# H_Driver.net
KiCad netlist of a schematic drawn in EAGLE
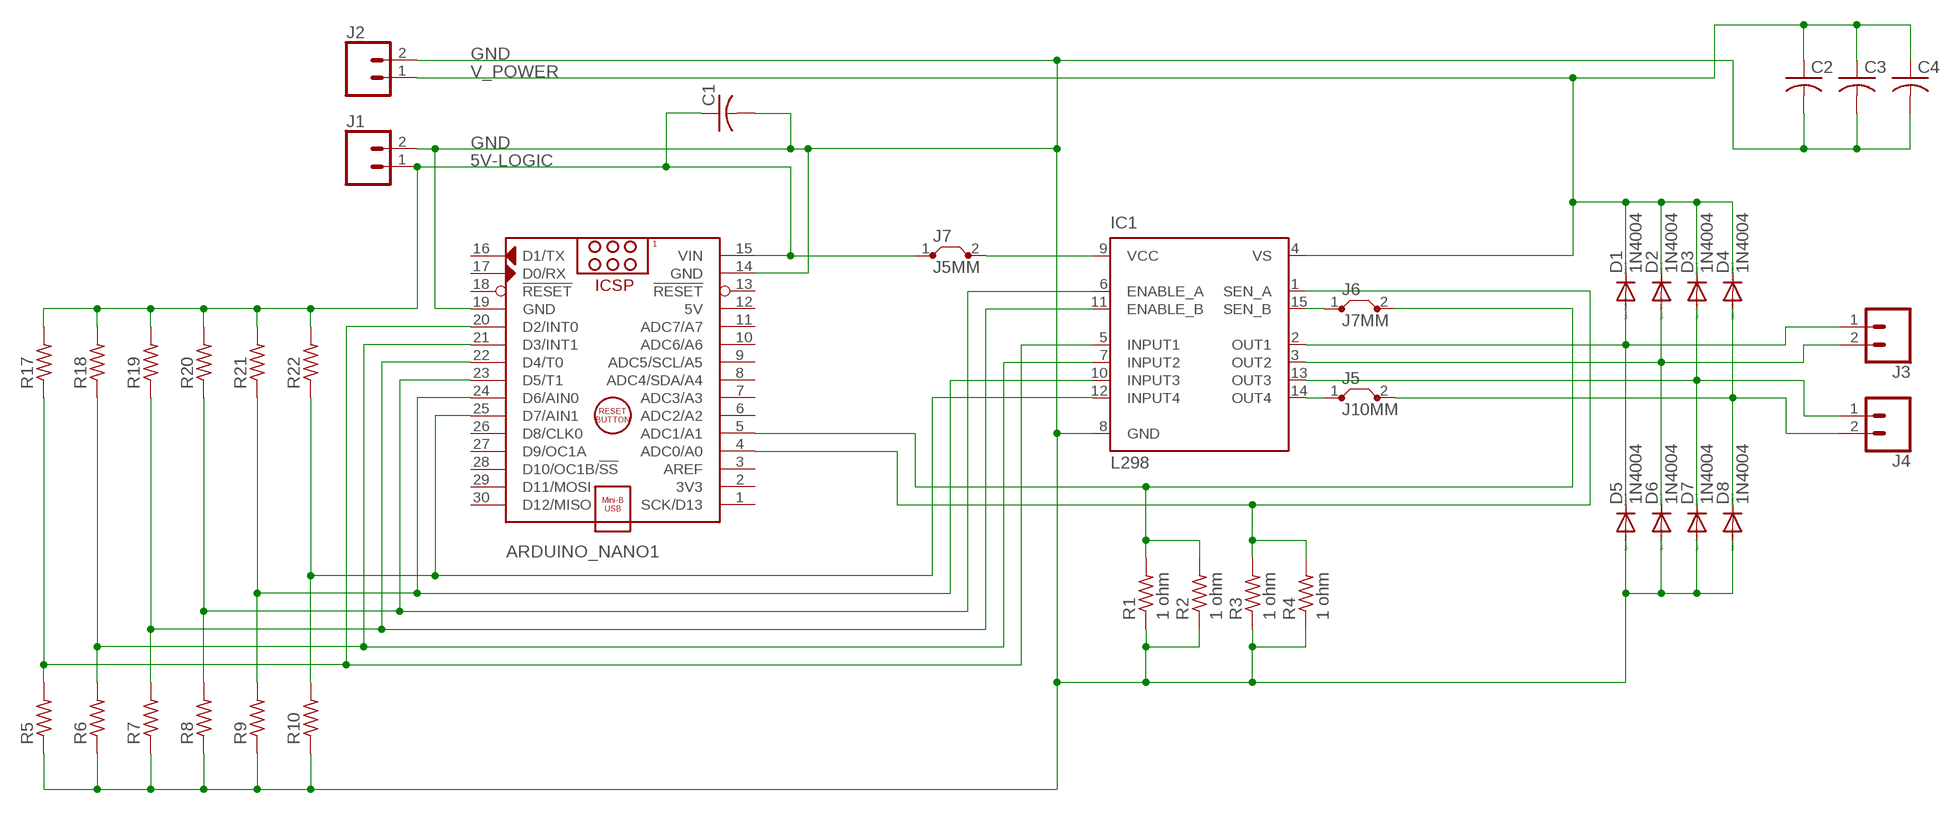
[diagram p0: schematic, sheet 1]

(export (version "E")
  (design (tool "Eeschema 10.0.6"))
  (components
    (comp (ref "ARDUINO_NANO1")
      (value "ARDUINO_NANO")
      (footprint "eagle-import:ARDUINO_NANO")
      (libsource (lib "eagle-import") (part "ARDUINO_NANO"))
    )
    (comp (ref "C1")
      (value "C-US050-025X075")
      (footprint "eagle-import:C050-025X075")
      (libsource (lib "eagle-import") (part "C-US050-025X075"))
    )
    (comp (ref "C2")
      (value "C-US050-025X075")
      (footprint "eagle-import:C050-025X075")
      (libsource (lib "eagle-import") (part "C-US050-025X075"))
    )
    (comp (ref "C3")
      (value "C-US050-025X075")
      (footprint "eagle-import:C050-025X075")
      (libsource (lib "eagle-import") (part "C-US050-025X075"))
    )
    (comp (ref "C4")
      (value "C-US050-025X075")
      (footprint "eagle-import:C050-025X075")
      (libsource (lib "eagle-import") (part "C-US050-025X075"))
    )
    (comp (ref "D1")
      (value "1N4004")
      (footprint "eagle-import:DO41-10")
      (libsource (lib "eagle-import") (part "1N4004"))
    )
    (comp (ref "D2")
      (value "1N4004")
      (footprint "eagle-import:DO41-10")
      (libsource (lib "eagle-import") (part "1N4004"))
    )
    (comp (ref "D3")
      (value "1N4004")
      (footprint "eagle-import:DO41-10")
      (libsource (lib "eagle-import") (part "1N4004"))
    )
    (comp (ref "D4")
      (value "1N4004")
      (footprint "eagle-import:DO41-10")
      (libsource (lib "eagle-import") (part "1N4004"))
    )
    (comp (ref "D5")
      (value "1N4004")
      (footprint "eagle-import:DO41-10")
      (libsource (lib "eagle-import") (part "1N4004"))
    )
    (comp (ref "D6")
      (value "1N4004")
      (footprint "eagle-import:DO41-10")
      (libsource (lib "eagle-import") (part "1N4004"))
    )
    (comp (ref "D7")
      (value "1N4004")
      (footprint "eagle-import:DO41-10")
      (libsource (lib "eagle-import") (part "1N4004"))
    )
    (comp (ref "D8")
      (value "1N4004")
      (footprint "eagle-import:DO41-10")
      (libsource (lib "eagle-import") (part "1N4004"))
    )
    (comp (ref "IC1")
      (value "L298")
      (footprint "eagle-import:MULTIWATT-15")
      (fields (field (name "MPN") "L298N"))
      (libsource (lib "eagle-import") (part "L298"))
    )
    (comp (ref "J1")
      (value "CONN_023.5MM_LOCK")
      (footprint "eagle-import:SCREWTERMINAL-3.5MM-2_LOCK")
      (libsource (lib "eagle-import") (part "CONN_023.5MM_LOCK"))
    )
    (comp (ref "J2")
      (value "CONN_023.5MM_LOCK")
      (footprint "eagle-import:SCREWTERMINAL-3.5MM-2_LOCK")
      (libsource (lib "eagle-import") (part "CONN_023.5MM_LOCK"))
    )
    (comp (ref "J3")
      (value "CONN_023.5MM_LOCK")
      (footprint "eagle-import:SCREWTERMINAL-3.5MM-2_LOCK")
      (libsource (lib "eagle-import") (part "CONN_023.5MM_LOCK"))
    )
    (comp (ref "J4")
      (value "CONN_023.5MM_LOCK")
      (footprint "eagle-import:SCREWTERMINAL-3.5MM-2_LOCK")
      (libsource (lib "eagle-import") (part "CONN_023.5MM_LOCK"))
    )
    (comp (ref "J5")
      (value "J10MM")
      (footprint "eagle-import:10")
      (libsource (lib "eagle-import") (part "J10MM"))
    )
    (comp (ref "J6")
      (value "J7MM")
      (footprint "eagle-import:07")
      (libsource (lib "eagle-import") (part "J7MM"))
    )
    (comp (ref "J7")
      (value "J5MM")
      (footprint "eagle-import:05")
      (libsource (lib "eagle-import") (part "J5MM"))
    )
    (comp (ref "R1")
      (value "1 ohm")
      (footprint "eagle-import:0204_7")
      (libsource (lib "eagle-import") (part "R-US_0204/7"))
    )
    (comp (ref "R2")
      (value "1 ohm")
      (footprint "eagle-import:0204_7")
      (libsource (lib "eagle-import") (part "R-US_0204/7"))
    )
    (comp (ref "R3")
      (value "1 ohm")
      (footprint "eagle-import:0204_7")
      (libsource (lib "eagle-import") (part "R-US_0204/7"))
    )
    (comp (ref "R4")
      (value "1 ohm")
      (footprint "eagle-import:0204_7")
      (libsource (lib "eagle-import") (part "R-US_0204/7"))
    )
    (comp (ref "R5")
      (value "R-US_0204/7")
      (footprint "eagle-import:0204_7")
      (libsource (lib "eagle-import") (part "R-US_0204/7"))
    )
    (comp (ref "R6")
      (value "R-US_0204/7")
      (footprint "eagle-import:0204_7")
      (libsource (lib "eagle-import") (part "R-US_0204/7"))
    )
    (comp (ref "R7")
      (value "R-US_0204/7")
      (footprint "eagle-import:0204_7")
      (libsource (lib "eagle-import") (part "R-US_0204/7"))
    )
    (comp (ref "R8")
      (value "R-US_0204/7")
      (footprint "eagle-import:0204_7")
      (libsource (lib "eagle-import") (part "R-US_0204/7"))
    )
    (comp (ref "R9")
      (value "R-US_0204/7")
      (footprint "eagle-import:0204_7")
      (libsource (lib "eagle-import") (part "R-US_0204/7"))
    )
    (comp (ref "R10")
      (value "R-US_0204/7")
      (footprint "eagle-import:0204_7")
      (libsource (lib "eagle-import") (part "R-US_0204/7"))
    )
    (comp (ref "R17")
      (value "R-US_0204/7")
      (footprint "eagle-import:0204_7")
      (libsource (lib "eagle-import") (part "R-US_0204/7"))
    )
    (comp (ref "R18")
      (value "R-US_0204/7")
      (footprint "eagle-import:0204_7")
      (libsource (lib "eagle-import") (part "R-US_0204/7"))
    )
    (comp (ref "R19")
      (value "R-US_0204/7")
      (footprint "eagle-import:0204_7")
      (libsource (lib "eagle-import") (part "R-US_0204/7"))
    )
    (comp (ref "R20")
      (value "R-US_0204/7")
      (footprint "eagle-import:0204_7")
      (libsource (lib "eagle-import") (part "R-US_0204/7"))
    )
    (comp (ref "R21")
      (value "R-US_0204/7")
      (footprint "eagle-import:0204_7")
      (libsource (lib "eagle-import") (part "R-US_0204/7"))
    )
    (comp (ref "R22")
      (value "R-US_0204/7")
      (footprint "eagle-import:0204_7")
      (libsource (lib "eagle-import") (part "R-US_0204/7"))
    )
  )
  (nets
    (net (code "1") (name "/5V") (class "Default")
      (node (ref "ARDUINO_NANO1") (pin "12") (pinfunction "5V_12") (pintype "power_in"))
    )
    (net (code "2") (name "/5V-LOGIC") (class "Default")
      (node (ref "ARDUINO_NANO1") (pin "15") (pinfunction "VIN_15") (pintype "power_in"))
      (node (ref "C1") (pin "1") (pinfunction "1_1") (pintype "passive"))
      (node (ref "J1") (pin "1") (pinfunction "1_1") (pintype "passive"))
      (node (ref "J7") (pin "1") (pinfunction "1_1") (pintype "passive"))
      (node (ref "R17") (pin "2") (pinfunction "2_2") (pintype "passive"))
      (node (ref "R18") (pin "2") (pinfunction "2_2") (pintype "passive"))
      (node (ref "R19") (pin "2") (pinfunction "2_2") (pintype "passive"))
      (node (ref "R20") (pin "2") (pinfunction "2_2") (pintype "passive"))
      (node (ref "R21") (pin "2") (pinfunction "2_2") (pintype "passive"))
      (node (ref "R22") (pin "2") (pinfunction "2_2") (pintype "passive"))
    )
    (net (code "3") (name "/GND") (class "Default")
      (node (ref "ARDUINO_NANO1") (pin "14") (pinfunction "GND_14") (pintype "power_in"))
      (node (ref "ARDUINO_NANO1") (pin "19") (pinfunction "GND_19") (pintype "power_in"))
      (node (ref "C1") (pin "2") (pinfunction "2_2") (pintype "passive"))
      (node (ref "C2") (pin "2") (pinfunction "2_2") (pintype "passive"))
      (node (ref "C3") (pin "2") (pinfunction "2_2") (pintype "passive"))
      (node (ref "C4") (pin "2") (pinfunction "2_2") (pintype "passive"))
      (node (ref "D5") (pin "A") (pinfunction "A_A") (pintype "passive"))
      (node (ref "D6") (pin "A") (pinfunction "A_A") (pintype "passive"))
      (node (ref "D7") (pin "A") (pinfunction "A_A") (pintype "passive"))
      (node (ref "D8") (pin "A") (pinfunction "A_A") (pintype "passive"))
      (node (ref "IC1") (pin "8") (pinfunction "GND_8") (pintype "power_in"))
      (node (ref "J1") (pin "2") (pinfunction "2_2") (pintype "passive"))
      (node (ref "J2") (pin "2") (pinfunction "2_2") (pintype "passive"))
      (node (ref "R1") (pin "1") (pinfunction "1_1") (pintype "passive"))
      (node (ref "R10") (pin "1") (pinfunction "1_1") (pintype "passive"))
      (node (ref "R2") (pin "1") (pinfunction "1_1") (pintype "passive"))
      (node (ref "R3") (pin "1") (pinfunction "1_1") (pintype "passive"))
      (node (ref "R4") (pin "1") (pinfunction "1_1") (pintype "passive"))
      (node (ref "R5") (pin "1") (pinfunction "1_1") (pintype "passive"))
      (node (ref "R6") (pin "1") (pinfunction "1_1") (pintype "passive"))
      (node (ref "R7") (pin "1") (pinfunction "1_1") (pintype "passive"))
      (node (ref "R8") (pin "1") (pinfunction "1_1") (pintype "passive"))
      (node (ref "R9") (pin "1") (pinfunction "1_1") (pintype "passive"))
    )
    (net (code "4") (name "/V_POWER") (class "Default")
      (node (ref "C2") (pin "1") (pinfunction "1_1") (pintype "passive"))
      (node (ref "C3") (pin "1") (pinfunction "1_1") (pintype "passive"))
      (node (ref "C4") (pin "1") (pinfunction "1_1") (pintype "passive"))
      (node (ref "D1") (pin "C") (pinfunction "C_C") (pintype "passive"))
      (node (ref "D2") (pin "C") (pinfunction "C_C") (pintype "passive"))
      (node (ref "D3") (pin "C") (pinfunction "C_C") (pintype "passive"))
      (node (ref "D4") (pin "C") (pinfunction "C_C") (pintype "passive"))
      (node (ref "IC1") (pin "4") (pinfunction "VS_4") (pintype "power_in"))
      (node (ref "J2") (pin "1") (pinfunction "1_1") (pintype "passive"))
    )
    (net (code "5") (name "Net-(ARDUINO_NANO1-ADC0{slash}A0)") (class "Default")
      (node (ref "ARDUINO_NANO1") (pin "4") (pinfunction "ADC0/A0_4") (pintype "bidirectional"))
      (node (ref "IC1") (pin "1") (pinfunction "SEN_A_1") (pintype "input"))
      (node (ref "R3") (pin "2") (pinfunction "2_2") (pintype "passive"))
      (node (ref "R4") (pin "2") (pinfunction "2_2") (pintype "passive"))
    )
    (net (code "6") (name "Net-(ARDUINO_NANO1-ADC1{slash}A1)") (class "Default")
      (node (ref "ARDUINO_NANO1") (pin "5") (pinfunction "ADC1/A1_5") (pintype "bidirectional"))
      (node (ref "J6") (pin "2") (pinfunction "2_2") (pintype "passive"))
      (node (ref "R1") (pin "2") (pinfunction "2_2") (pintype "passive"))
      (node (ref "R2") (pin "2") (pinfunction "2_2") (pintype "passive"))
    )
    (net (code "7") (name "Net-(ARDUINO_NANO1-D2{slash}INT0)") (class "Default")
      (node (ref "ARDUINO_NANO1") (pin "20") (pinfunction "D2/INT0_20") (pintype "bidirectional"))
      (node (ref "IC1") (pin "5") (pinfunction "INPUT1_5") (pintype "input"))
      (node (ref "R17") (pin "1") (pinfunction "1_1") (pintype "passive"))
      (node (ref "R5") (pin "2") (pinfunction "2_2") (pintype "passive"))
    )
    (net (code "8") (name "Net-(ARDUINO_NANO1-D3{slash}INT1)") (class "Default")
      (node (ref "ARDUINO_NANO1") (pin "21") (pinfunction "D3/INT1_21") (pintype "bidirectional"))
      (node (ref "IC1") (pin "7") (pinfunction "INPUT2_7") (pintype "input"))
      (node (ref "R18") (pin "1") (pinfunction "1_1") (pintype "passive"))
      (node (ref "R6") (pin "2") (pinfunction "2_2") (pintype "passive"))
    )
    (net (code "9") (name "Net-(ARDUINO_NANO1-D4{slash}T0)") (class "Default")
      (node (ref "ARDUINO_NANO1") (pin "22") (pinfunction "D4/T0_22") (pintype "bidirectional"))
      (node (ref "IC1") (pin "11") (pinfunction "ENABLE_B_11") (pintype "input"))
      (node (ref "R19") (pin "1") (pinfunction "1_1") (pintype "passive"))
      (node (ref "R7") (pin "2") (pinfunction "2_2") (pintype "passive"))
    )
    (net (code "10") (name "Net-(ARDUINO_NANO1-D5{slash}T1)") (class "Default")
      (node (ref "ARDUINO_NANO1") (pin "23") (pinfunction "D5/T1_23") (pintype "bidirectional"))
      (node (ref "IC1") (pin "6") (pinfunction "ENABLE_A_6") (pintype "input"))
      (node (ref "R20") (pin "1") (pinfunction "1_1") (pintype "passive"))
      (node (ref "R8") (pin "2") (pinfunction "2_2") (pintype "passive"))
    )
    (net (code "11") (name "Net-(ARDUINO_NANO1-D6{slash}AIN0)") (class "Default")
      (node (ref "ARDUINO_NANO1") (pin "24") (pinfunction "D6/AIN0_24") (pintype "bidirectional"))
      (node (ref "IC1") (pin "10") (pinfunction "INPUT3_10") (pintype "input"))
      (node (ref "R21") (pin "1") (pinfunction "1_1") (pintype "passive"))
      (node (ref "R9") (pin "2") (pinfunction "2_2") (pintype "passive"))
    )
    (net (code "12") (name "Net-(ARDUINO_NANO1-D7{slash}AIN1)") (class "Default")
      (node (ref "ARDUINO_NANO1") (pin "25") (pinfunction "D7/AIN1_25") (pintype "bidirectional"))
      (node (ref "IC1") (pin "12") (pinfunction "INPUT4_12") (pintype "input"))
      (node (ref "R10") (pin "2") (pinfunction "2_2") (pintype "passive"))
      (node (ref "R22") (pin "1") (pinfunction "1_1") (pintype "passive"))
    )
    (net (code "13") (name "Net-(D4-PadA)") (class "Default")
      (node (ref "D4") (pin "A") (pinfunction "A_A") (pintype "passive"))
      (node (ref "D8") (pin "C") (pinfunction "C_C") (pintype "passive"))
      (node (ref "J4") (pin "2") (pinfunction "2_2") (pintype "passive"))
      (node (ref "J5") (pin "2") (pinfunction "2_2") (pintype "passive"))
    )
    (net (code "14") (name "Net-(IC1-OUT1)") (class "Default")
      (node (ref "D1") (pin "A") (pinfunction "A_A") (pintype "passive"))
      (node (ref "D5") (pin "C") (pinfunction "C_C") (pintype "passive"))
      (node (ref "IC1") (pin "2") (pinfunction "OUT1_2") (pintype "output"))
      (node (ref "J3") (pin "1") (pinfunction "1_1") (pintype "passive"))
    )
    (net (code "15") (name "Net-(IC1-OUT2)") (class "Default")
      (node (ref "D2") (pin "A") (pinfunction "A_A") (pintype "passive"))
      (node (ref "D6") (pin "C") (pinfunction "C_C") (pintype "passive"))
      (node (ref "IC1") (pin "3") (pinfunction "OUT2_3") (pintype "output"))
      (node (ref "J3") (pin "2") (pinfunction "2_2") (pintype "passive"))
    )
    (net (code "16") (name "Net-(IC1-OUT3)") (class "Default")
      (node (ref "D3") (pin "A") (pinfunction "A_A") (pintype "passive"))
      (node (ref "D7") (pin "C") (pinfunction "C_C") (pintype "passive"))
      (node (ref "IC1") (pin "13") (pinfunction "OUT3_13") (pintype "output"))
      (node (ref "J4") (pin "1") (pinfunction "1_1") (pintype "passive"))
    )
    (net (code "17") (name "Net-(IC1-OUT4)") (class "Default")
      (node (ref "IC1") (pin "14") (pinfunction "OUT4_14") (pintype "output"))
      (node (ref "J5") (pin "1") (pinfunction "1_1") (pintype "passive"))
    )
    (net (code "18") (name "Net-(IC1-SEN_B)") (class "Default")
      (node (ref "IC1") (pin "15") (pinfunction "SEN_B_15") (pintype "input"))
      (node (ref "J6") (pin "1") (pinfunction "1_1") (pintype "passive"))
    )
    (net (code "19") (name "Net-(IC1-VCC)") (class "Default")
      (node (ref "IC1") (pin "9") (pinfunction "VCC_9") (pintype "power_in"))
      (node (ref "J7") (pin "2") (pinfunction "2_2") (pintype "passive"))
    )
    (net (code "20") (name "unconnected-(ARDUINO_NANO1-3V3-Pad2)") (class "Default")
      (node (ref "ARDUINO_NANO1") (pin "2") (pinfunction "3V3_2") (pintype "output"))
    )
    (net (code "21") (name "unconnected-(ARDUINO_NANO1-ADC2{slash}A2-Pad6)") (class "Default")
      (node (ref "ARDUINO_NANO1") (pin "6") (pinfunction "ADC2/A2_6") (pintype "bidirectional"))
    )
    (net (code "22") (name "unconnected-(ARDUINO_NANO1-ADC3{slash}A3-Pad7)") (class "Default")
      (node (ref "ARDUINO_NANO1") (pin "7") (pinfunction "ADC3/A3_7") (pintype "bidirectional"))
    )
    (net (code "23") (name "unconnected-(ARDUINO_NANO1-ADC4{slash}SDA{slash}A4-Pad8)") (class "Default")
      (node (ref "ARDUINO_NANO1") (pin "8") (pinfunction "ADC4/SDA/A4_8") (pintype "bidirectional"))
    )
    (net (code "24") (name "unconnected-(ARDUINO_NANO1-ADC5{slash}SCL{slash}A5-Pad9)") (class "Default")
      (node (ref "ARDUINO_NANO1") (pin "9") (pinfunction "ADC5/SCL/A5_9") (pintype "bidirectional"))
    )
    (net (code "25") (name "unconnected-(ARDUINO_NANO1-ADC6{slash}A6-Pad10)") (class "Default")
      (node (ref "ARDUINO_NANO1") (pin "10") (pinfunction "ADC6/A6_10") (pintype "bidirectional"))
    )
    (net (code "26") (name "unconnected-(ARDUINO_NANO1-ADC7{slash}A7-Pad11)") (class "Default")
      (node (ref "ARDUINO_NANO1") (pin "11") (pinfunction "ADC7/A7_11") (pintype "bidirectional"))
    )
    (net (code "27") (name "unconnected-(ARDUINO_NANO1-AREF-Pad3)") (class "Default")
      (node (ref "ARDUINO_NANO1") (pin "3") (pinfunction "AREF_3") (pintype "input"))
    )
    (net (code "28") (name "unconnected-(ARDUINO_NANO1-D0{slash}RX-Pad17)") (class "Default")
      (node (ref "ARDUINO_NANO1") (pin "17") (pinfunction "D0/RX_17") (pintype "bidirectional"))
    )
    (net (code "29") (name "unconnected-(ARDUINO_NANO1-D1{slash}TX-Pad16)") (class "Default")
      (node (ref "ARDUINO_NANO1") (pin "16") (pinfunction "D1/TX_16") (pintype "bidirectional"))
    )
    (net (code "30") (name "unconnected-(ARDUINO_NANO1-D8{slash}CLK0-Pad26)") (class "Default")
      (node (ref "ARDUINO_NANO1") (pin "26") (pinfunction "D8/CLK0_26") (pintype "bidirectional"))
    )
    (net (code "31") (name "unconnected-(ARDUINO_NANO1-D9{slash}OC1A-Pad27)") (class "Default")
      (node (ref "ARDUINO_NANO1") (pin "27") (pinfunction "D9/OC1A_27") (pintype "bidirectional"))
    )
    (net (code "32") (name "unconnected-(ARDUINO_NANO1-D10{slash}OC1B{slash}~{SS}-Pad28)") (class "Default")
      (node (ref "ARDUINO_NANO1") (pin "28") (pinfunction "D10/OC1B/~{SS}_28") (pintype "bidirectional"))
    )
    (net (code "33") (name "unconnected-(ARDUINO_NANO1-D11{slash}MOSI-Pad29)") (class "Default")
      (node (ref "ARDUINO_NANO1") (pin "29") (pinfunction "D11/MOSI_29") (pintype "bidirectional"))
    )
    (net (code "34") (name "unconnected-(ARDUINO_NANO1-D12{slash}MISO-Pad30)") (class "Default")
      (node (ref "ARDUINO_NANO1") (pin "30") (pinfunction "D12/MISO_30") (pintype "bidirectional"))
    )
    (net (code "35") (name "unconnected-(ARDUINO_NANO1-SCK{slash}D13-Pad1)") (class "Default")
      (node (ref "ARDUINO_NANO1") (pin "1") (pinfunction "SCK/D13_1") (pintype "bidirectional"))
    )
    (net (code "36") (name "unconnected-(ARDUINO_NANO1-~{RESET}-Pad13)") (class "Default")
      (node (ref "ARDUINO_NANO1") (pin "13") (pinfunction "~{RESET}_13") (pintype "input"))
    )
    (net (code "37") (name "unconnected-(ARDUINO_NANO1-~{RESET}-Pad18)") (class "Default")
      (node (ref "ARDUINO_NANO1") (pin "18") (pinfunction "~{RESET}_18") (pintype "input"))
    )
  )
)
